# lcd_display_board.net
KiCad netlist of a schematic drawn in EAGLE
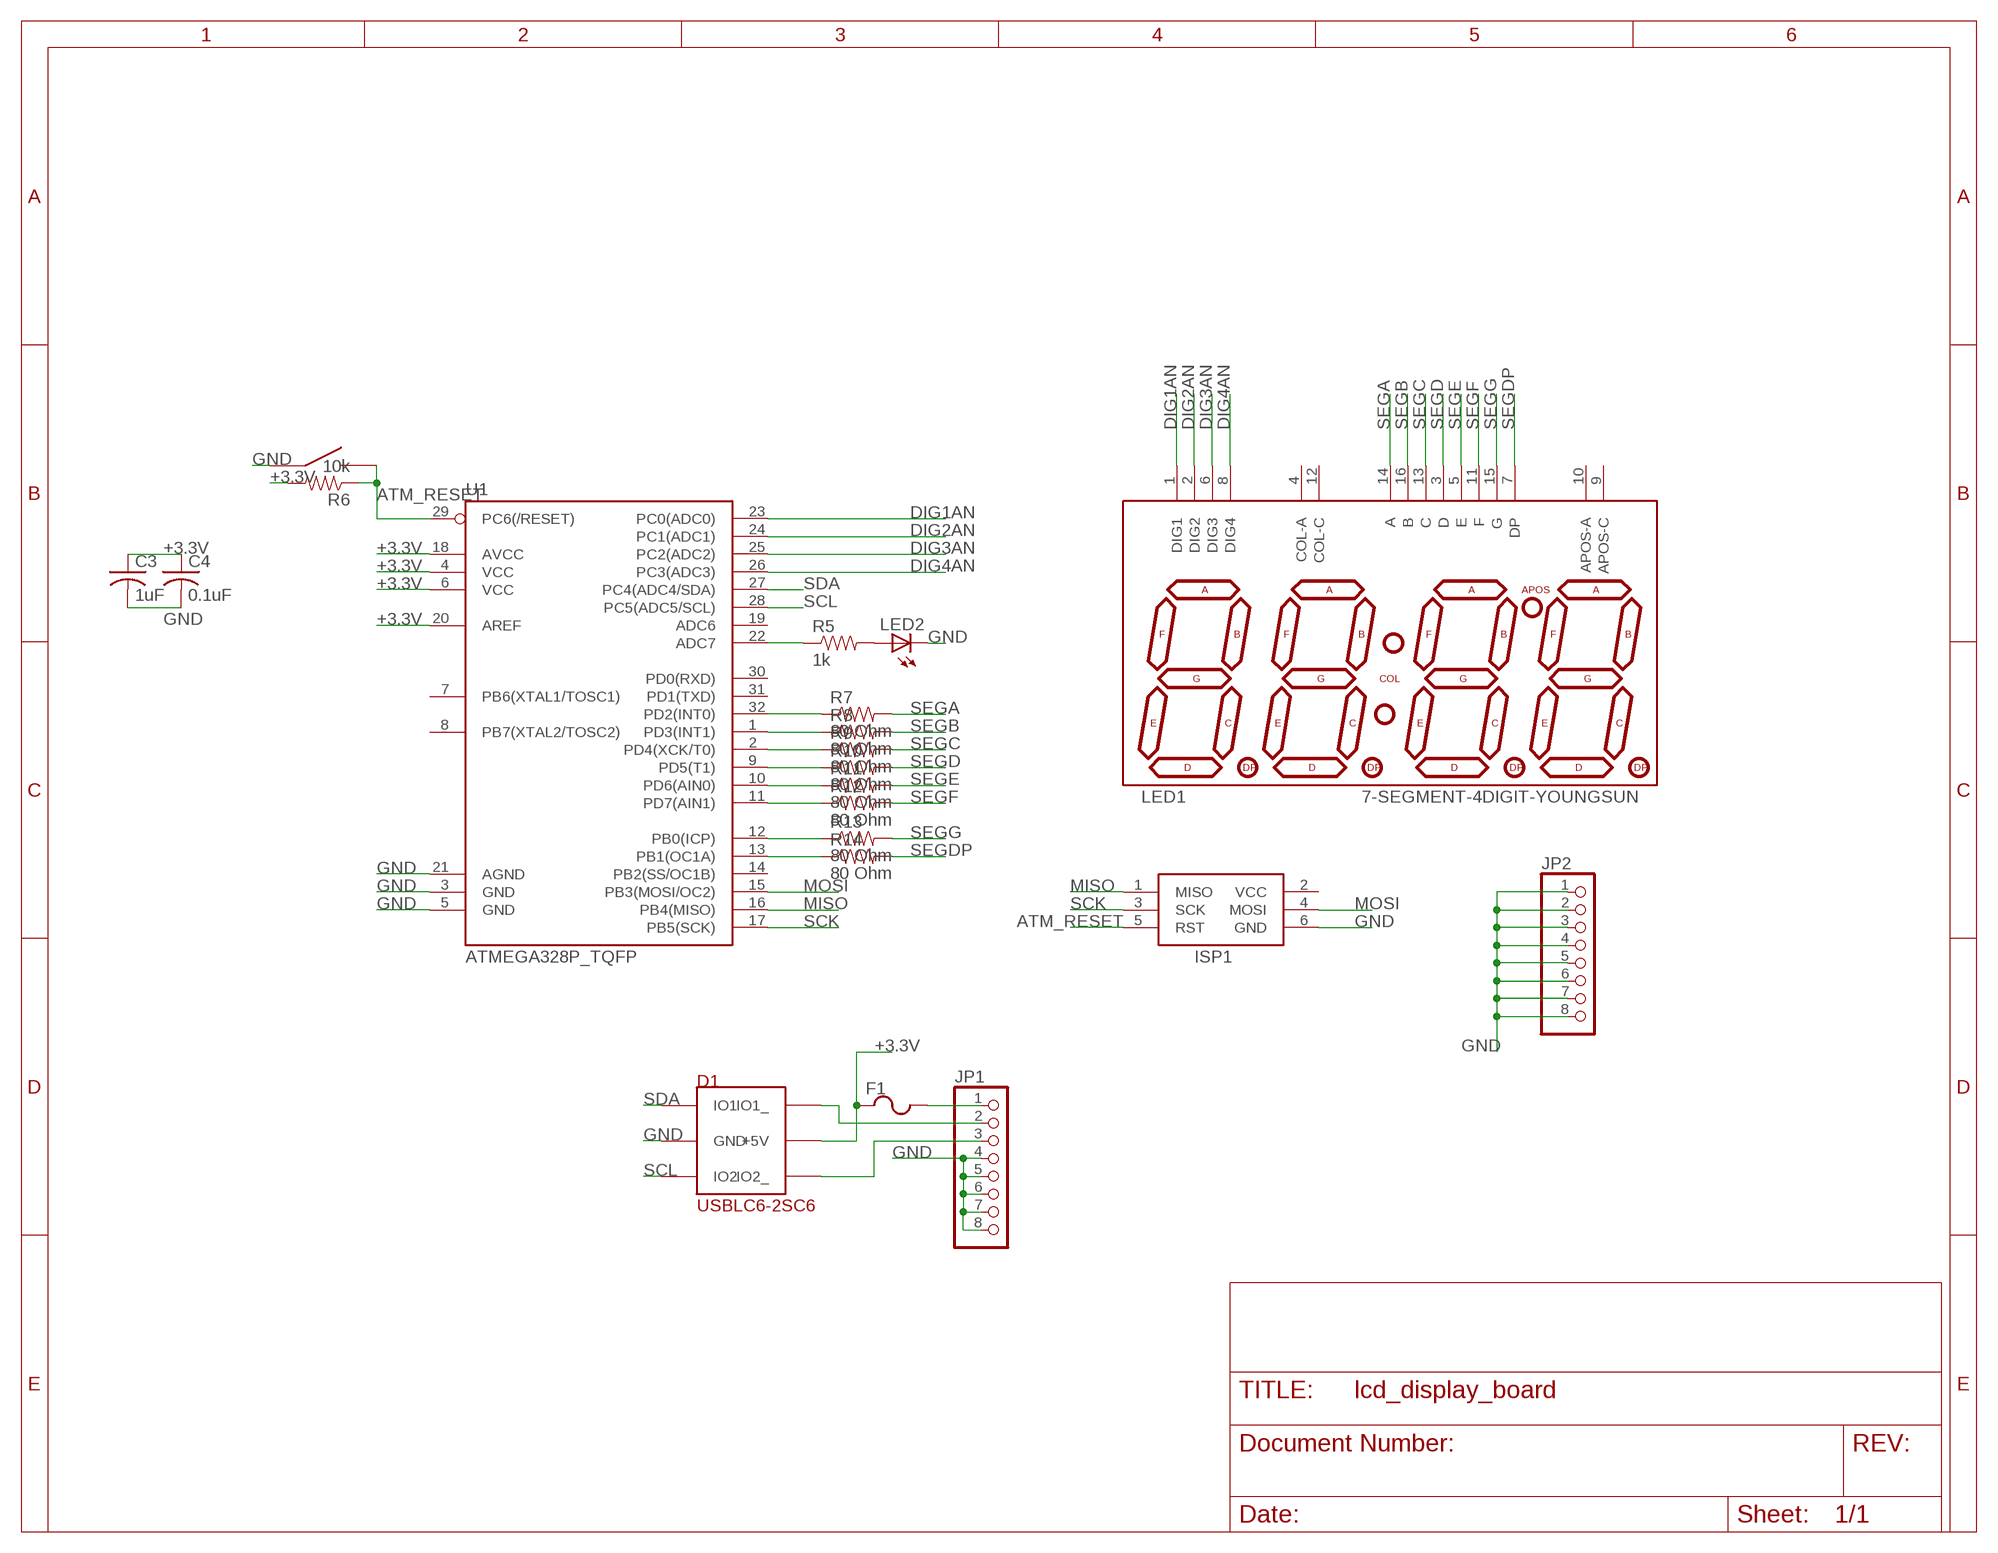
[diagram p0: schematic, sheet 1]

(export (version "E")
  (design (tool "Eeschema 10.0.6"))
  (components
    (comp (ref "C3")
      (value "1uF")
      (footprint "eagle-import:C0805")
      (libsource (lib "eagle-import") (part "C-USC0805"))
    )
    (comp (ref "C4")
      (value "0.1uF")
      (footprint "eagle-import:C0805")
      (libsource (lib "eagle-import") (part "C-USC0805"))
    )
    (comp (ref "D1")
      (value "USBLC6-2SC6")
      (footprint "eagle-import:USBLC6-2SC6")
      (libsource (lib "eagle-import") (part "USBLC6-2SC6"))
    )
    (comp (ref "F1")
      (value "POLYFUSE")
      (footprint "eagle-import:1206")
      (libsource (lib "eagle-import") (part "POLYFUSE"))
    )
    (comp (ref "ISP1")
      (value "AVRISP-BOX")
      (footprint "eagle-import:AVRISP-BOX")
      (libsource (lib "eagle-import") (part "AVRISP-BOX"))
    )
    (comp (ref "JP1")
      (value "PINHD-1X8BIG")
      (footprint "eagle-import:1X08-BIG")
      (libsource (lib "eagle-import") (part "PINHD-1X8BIG"))
    )
    (comp (ref "JP2")
      (value "PINHD-1X8BIG")
      (footprint "eagle-import:1X08-BIG")
      (libsource (lib "eagle-import") (part "PINHD-1X8BIG"))
    )
    (comp (ref "LED1")
      (value "7-SEGMENT-4DIGIT-YOUNGSUN")
      (footprint "eagle-import:7-SEGMENT-4DIGIT-YOUNGSUN")
      (libsource (lib "eagle-import") (part "7-SEGMENT-4DIGIT-YOUNGSUN"))
    )
    (comp (ref "LED2")
      (value "LEDCHIPLED_0805")
      (footprint "eagle-import:CHIPLED_0805")
      (libsource (lib "eagle-import") (part "LEDCHIPLED_0805"))
    )
    (comp (ref "R5")
      (value "1k")
      (footprint "eagle-import:0603-RES")
      (libsource (lib "eagle-import") (part "RESISTOR0603-RES"))
    )
    (comp (ref "R6")
      (value "10k")
      (footprint "eagle-import:0603-RES")
      (libsource (lib "eagle-import") (part "RESISTOR0603-RES"))
    )
    (comp (ref "R7")
      (value "80 Ohm")
      (footprint "eagle-import:0603-RES")
      (libsource (lib "eagle-import") (part "RESISTOR0603-RES"))
    )
    (comp (ref "R8")
      (value "80 Ohm")
      (footprint "eagle-import:0603-RES")
      (libsource (lib "eagle-import") (part "RESISTOR0603-RES"))
    )
    (comp (ref "R9")
      (value "80 Ohm")
      (footprint "eagle-import:0603-RES")
      (libsource (lib "eagle-import") (part "RESISTOR0603-RES"))
    )
    (comp (ref "R10")
      (value "80 Ohm")
      (footprint "eagle-import:0603-RES")
      (libsource (lib "eagle-import") (part "RESISTOR0603-RES"))
    )
    (comp (ref "R11")
      (value "80 Ohm")
      (footprint "eagle-import:0603-RES")
      (libsource (lib "eagle-import") (part "RESISTOR0603-RES"))
    )
    (comp (ref "R12")
      (value "80 Ohm")
      (footprint "eagle-import:0603-RES")
      (libsource (lib "eagle-import") (part "RESISTOR0603-RES"))
    )
    (comp (ref "R13")
      (value "80 Ohm")
      (footprint "eagle-import:0603-RES")
      (libsource (lib "eagle-import") (part "RESISTOR0603-RES"))
    )
    (comp (ref "R14")
      (value "80 Ohm")
      (footprint "eagle-import:0603-RES")
      (libsource (lib "eagle-import") (part "RESISTOR0603-RES"))
    )
    (comp (ref "U$10")
      (value "EG4621CT-ND")
      (footprint "eagle-import:EG4621CT-ND")
      (libsource (lib "eagle-import") (part "EG4621CT-ND"))
    )
    (comp (ref "U1")
      (value "ATMEGA328P_TQFP")
      (footprint "eagle-import:TQFP32-08")
      (libsource (lib "eagle-import") (part "ATMEGA328P_TQFP"))
    )
  )
  (nets
    (net (code "1") (name "/+3.3V") (class "Default")
      (node (ref "C3") (pin "1") (pinfunction "1_1") (pintype "passive"))
      (node (ref "C4") (pin "1") (pinfunction "1_1") (pintype "passive"))
      (node (ref "D1") (pin "P$5") (pinfunction "+5V_P$5") (pintype "bidirectional"))
      (node (ref "F1") (pin "1") (pinfunction "1_1") (pintype "passive"))
      (node (ref "R6") (pin "2") (pinfunction "2_2") (pintype "passive"))
      (node (ref "U1") (pin "18") (pinfunction "AVCC_18") (pintype "bidirectional"))
      (node (ref "U1") (pin "20") (pinfunction "AREF_20") (pintype "bidirectional"))
      (node (ref "U1") (pin "4") (pinfunction "VCC_4") (pintype "bidirectional"))
      (node (ref "U1") (pin "6") (pinfunction "VCC_6") (pintype "bidirectional"))
    )
    (net (code "2") (name "/ATM_RESET") (class "Default")
      (node (ref "ISP1") (pin "5") (pinfunction "RST_5") (pintype "output"))
      (node (ref "R6") (pin "1") (pinfunction "1_1") (pintype "passive"))
      (node (ref "U$10") (pin "P$3") (pinfunction "P$2_P$3") (pintype "bidirectional"))
      (node (ref "U$10") (pin "P$4") (pinfunction "P$2_P$4") (pintype "bidirectional"))
      (node (ref "U1") (pin "29") (pinfunction "PC6(/RESET)_29") (pintype "bidirectional"))
    )
    (net (code "3") (name "/DIG1AN") (class "Default")
      (node (ref "LED1") (pin "1") (pinfunction "DIG1_1") (pintype "bidirectional"))
      (node (ref "U1") (pin "23") (pinfunction "PC0(ADC0)_23") (pintype "bidirectional"))
    )
    (net (code "4") (name "/DIG2AN") (class "Default")
      (node (ref "LED1") (pin "2") (pinfunction "DIG2_2") (pintype "bidirectional"))
      (node (ref "U1") (pin "24") (pinfunction "PC1(ADC1)_24") (pintype "bidirectional"))
    )
    (net (code "5") (name "/DIG3AN") (class "Default")
      (node (ref "LED1") (pin "6") (pinfunction "DIG3_6") (pintype "bidirectional"))
      (node (ref "U1") (pin "25") (pinfunction "PC2(ADC2)_25") (pintype "bidirectional"))
    )
    (net (code "6") (name "/DIG4AN") (class "Default")
      (node (ref "LED1") (pin "8") (pinfunction "DIG4_8") (pintype "bidirectional"))
      (node (ref "U1") (pin "26") (pinfunction "PC3(ADC3)_26") (pintype "bidirectional"))
    )
    (net (code "7") (name "/GND") (class "Default")
      (node (ref "C3") (pin "2") (pinfunction "2_2") (pintype "passive"))
      (node (ref "C4") (pin "2") (pinfunction "2_2") (pintype "passive"))
      (node (ref "D1") (pin "P$2") (pinfunction "GND_P$2") (pintype "bidirectional"))
      (node (ref "ISP1") (pin "6") (pinfunction "GND_6") (pintype "power_in"))
      (node (ref "JP1") (pin "4") (pinfunction "4_4") (pintype "passive"))
      (node (ref "JP1") (pin "5") (pinfunction "5_5") (pintype "passive"))
      (node (ref "JP1") (pin "6") (pinfunction "6_6") (pintype "passive"))
      (node (ref "JP1") (pin "7") (pinfunction "7_7") (pintype "passive"))
      (node (ref "JP1") (pin "8") (pinfunction "8_8") (pintype "passive"))
      (node (ref "JP2") (pin "1") (pinfunction "1_1") (pintype "passive"))
      (node (ref "JP2") (pin "2") (pinfunction "2_2") (pintype "passive"))
      (node (ref "JP2") (pin "3") (pinfunction "3_3") (pintype "passive"))
      (node (ref "JP2") (pin "4") (pinfunction "4_4") (pintype "passive"))
      (node (ref "JP2") (pin "5") (pinfunction "5_5") (pintype "passive"))
      (node (ref "JP2") (pin "6") (pinfunction "6_6") (pintype "passive"))
      (node (ref "JP2") (pin "7") (pinfunction "7_7") (pintype "passive"))
      (node (ref "JP2") (pin "8") (pinfunction "8_8") (pintype "passive"))
      (node (ref "LED2") (pin "C") (pinfunction "C_C") (pintype "passive"))
      (node (ref "U$10") (pin "P$1") (pinfunction "P$1_P$1") (pintype "bidirectional"))
      (node (ref "U$10") (pin "P$2") (pinfunction "P$1_P$2") (pintype "bidirectional"))
      (node (ref "U1") (pin "21") (pinfunction "AGND_21") (pintype "bidirectional"))
      (node (ref "U1") (pin "3") (pinfunction "GND_3") (pintype "bidirectional"))
      (node (ref "U1") (pin "5") (pinfunction "GND_5") (pintype "bidirectional"))
    )
    (net (code "8") (name "/MISO") (class "Default")
      (node (ref "ISP1") (pin "1") (pinfunction "MISO_1") (pintype "input"))
      (node (ref "U1") (pin "16") (pinfunction "PB4(MISO)_16") (pintype "bidirectional"))
    )
    (net (code "9") (name "/MOSI") (class "Default")
      (node (ref "ISP1") (pin "4") (pinfunction "MOSI_4") (pintype "output"))
      (node (ref "U1") (pin "15") (pinfunction "PB3(MOSI/OC2)_15") (pintype "bidirectional"))
    )
    (net (code "10") (name "/SCK") (class "Default")
      (node (ref "ISP1") (pin "3") (pinfunction "SCK_3") (pintype "output"))
      (node (ref "U1") (pin "17") (pinfunction "PB5(SCK)_17") (pintype "bidirectional"))
    )
    (net (code "11") (name "/SCL") (class "Default")
      (node (ref "D1") (pin "P$3") (pinfunction "IO2_P$3") (pintype "bidirectional"))
      (node (ref "U1") (pin "28") (pinfunction "PC5(ADC5/SCL)_28") (pintype "bidirectional"))
    )
    (net (code "12") (name "/SDA") (class "Default")
      (node (ref "D1") (pin "P$1") (pinfunction "IO1_P$1") (pintype "bidirectional"))
      (node (ref "U1") (pin "27") (pinfunction "PC4(ADC4/SDA)_27") (pintype "bidirectional"))
    )
    (net (code "13") (name "/SEGA") (class "Default")
      (node (ref "LED1") (pin "14") (pinfunction "A_14") (pintype "bidirectional"))
      (node (ref "R7") (pin "2") (pinfunction "2_2") (pintype "passive"))
    )
    (net (code "14") (name "/SEGB") (class "Default")
      (node (ref "LED1") (pin "16") (pinfunction "B_16") (pintype "bidirectional"))
      (node (ref "R8") (pin "2") (pinfunction "2_2") (pintype "passive"))
    )
    (net (code "15") (name "/SEGC") (class "Default")
      (node (ref "LED1") (pin "13") (pinfunction "C_13") (pintype "bidirectional"))
      (node (ref "R9") (pin "2") (pinfunction "2_2") (pintype "passive"))
    )
    (net (code "16") (name "/SEGD") (class "Default")
      (node (ref "LED1") (pin "3") (pinfunction "D_3") (pintype "bidirectional"))
      (node (ref "R10") (pin "2") (pinfunction "2_2") (pintype "passive"))
    )
    (net (code "17") (name "/SEGDP") (class "Default")
      (node (ref "LED1") (pin "7") (pinfunction "DP_7") (pintype "bidirectional"))
      (node (ref "R14") (pin "2") (pinfunction "2_2") (pintype "passive"))
    )
    (net (code "18") (name "/SEGE") (class "Default")
      (node (ref "LED1") (pin "5") (pinfunction "E_5") (pintype "bidirectional"))
      (node (ref "R11") (pin "2") (pinfunction "2_2") (pintype "passive"))
    )
    (net (code "19") (name "/SEGF") (class "Default")
      (node (ref "LED1") (pin "11") (pinfunction "F_11") (pintype "bidirectional"))
      (node (ref "R12") (pin "2") (pinfunction "2_2") (pintype "passive"))
    )
    (net (code "20") (name "/SEGG") (class "Default")
      (node (ref "LED1") (pin "15") (pinfunction "G_15") (pintype "bidirectional"))
      (node (ref "R13") (pin "2") (pinfunction "2_2") (pintype "passive"))
    )
    (net (code "21") (name "/VCC") (class "Default")
      (node (ref "ISP1") (pin "2") (pinfunction "VCC_2") (pintype "power_in"))
    )
    (net (code "22") (name "Net-(D1-IO1_)") (class "Default")
      (node (ref "D1") (pin "P$6") (pinfunction "IO1__P$6") (pintype "bidirectional"))
      (node (ref "JP1") (pin "2") (pinfunction "2_2") (pintype "passive"))
    )
    (net (code "23") (name "Net-(D1-IO2_)") (class "Default")
      (node (ref "D1") (pin "P$4") (pinfunction "IO2__P$4") (pintype "bidirectional"))
      (node (ref "JP1") (pin "3") (pinfunction "3_3") (pintype "passive"))
    )
    (net (code "24") (name "Net-(F1-Pad2)") (class "Default")
      (node (ref "F1") (pin "2") (pinfunction "2_2") (pintype "passive"))
      (node (ref "JP1") (pin "1") (pinfunction "1_1") (pintype "passive"))
    )
    (net (code "25") (name "Net-(LED2-PadA)") (class "Default")
      (node (ref "LED2") (pin "A") (pinfunction "A_A") (pintype "passive"))
      (node (ref "R5") (pin "2") (pinfunction "2_2") (pintype "passive"))
    )
    (net (code "26") (name "Net-(U1-ADC7)") (class "Default")
      (node (ref "R5") (pin "1") (pinfunction "1_1") (pintype "passive"))
      (node (ref "U1") (pin "22") (pinfunction "ADC7_22") (pintype "bidirectional"))
    )
    (net (code "27") (name "Net-(U1-PB0(ICP))") (class "Default")
      (node (ref "R13") (pin "1") (pinfunction "1_1") (pintype "passive"))
      (node (ref "U1") (pin "12") (pinfunction "PB0(ICP)_12") (pintype "bidirectional"))
    )
    (net (code "28") (name "Net-(U1-PB1(OC1A))") (class "Default")
      (node (ref "R14") (pin "1") (pinfunction "1_1") (pintype "passive"))
      (node (ref "U1") (pin "13") (pinfunction "PB1(OC1A)_13") (pintype "bidirectional"))
    )
    (net (code "29") (name "Net-(U1-PD2(INT0))") (class "Default")
      (node (ref "R7") (pin "1") (pinfunction "1_1") (pintype "passive"))
      (node (ref "U1") (pin "32") (pinfunction "PD2(INT0)_32") (pintype "bidirectional"))
    )
    (net (code "30") (name "Net-(U1-PD3(INT1))") (class "Default")
      (node (ref "R8") (pin "1") (pinfunction "1_1") (pintype "passive"))
      (node (ref "U1") (pin "1") (pinfunction "PD3(INT1)_1") (pintype "bidirectional"))
    )
    (net (code "31") (name "Net-(U1-PD4(XCK{slash}T0))") (class "Default")
      (node (ref "R9") (pin "1") (pinfunction "1_1") (pintype "passive"))
      (node (ref "U1") (pin "2") (pinfunction "PD4(XCK/T0)_2") (pintype "bidirectional"))
    )
    (net (code "32") (name "Net-(U1-PD5(T1))") (class "Default")
      (node (ref "R10") (pin "1") (pinfunction "1_1") (pintype "passive"))
      (node (ref "U1") (pin "9") (pinfunction "PD5(T1)_9") (pintype "bidirectional"))
    )
    (net (code "33") (name "Net-(U1-PD6(AIN0))") (class "Default")
      (node (ref "R11") (pin "1") (pinfunction "1_1") (pintype "passive"))
      (node (ref "U1") (pin "10") (pinfunction "PD6(AIN0)_10") (pintype "bidirectional"))
    )
    (net (code "34") (name "Net-(U1-PD7(AIN1))") (class "Default")
      (node (ref "R12") (pin "1") (pinfunction "1_1") (pintype "passive"))
      (node (ref "U1") (pin "11") (pinfunction "PD7(AIN1)_11") (pintype "bidirectional"))
    )
    (net (code "35") (name "unconnected-(LED1-APOS-A-Pad10)") (class "Default")
      (node (ref "LED1") (pin "10") (pinfunction "APOS-A_10") (pintype "bidirectional"))
    )
    (net (code "36") (name "unconnected-(LED1-APOS-C-Pad9)") (class "Default")
      (node (ref "LED1") (pin "9") (pinfunction "APOS-C_9") (pintype "bidirectional"))
    )
    (net (code "37") (name "unconnected-(LED1-COL-A-Pad4)") (class "Default")
      (node (ref "LED1") (pin "4") (pinfunction "COL-A_4") (pintype "bidirectional"))
    )
    (net (code "38") (name "unconnected-(LED1-COL-C-Pad12)") (class "Default")
      (node (ref "LED1") (pin "12") (pinfunction "COL-C_12") (pintype "bidirectional"))
    )
    (net (code "39") (name "unconnected-(U1-ADC6-Pad19)") (class "Default")
      (node (ref "U1") (pin "19") (pinfunction "ADC6_19") (pintype "bidirectional"))
    )
    (net (code "40") (name "unconnected-(U1-PB2(SS{slash}OC1B)-Pad14)") (class "Default")
      (node (ref "U1") (pin "14") (pinfunction "PB2(SS/OC1B)_14") (pintype "bidirectional"))
    )
    (net (code "41") (name "unconnected-(U1-PB6(XTAL1{slash}TOSC1)-Pad7)") (class "Default")
      (node (ref "U1") (pin "7") (pinfunction "PB6(XTAL1/TOSC1)_7") (pintype "bidirectional"))
    )
    (net (code "42") (name "unconnected-(U1-PB7(XTAL2{slash}TOSC2)-Pad8)") (class "Default")
      (node (ref "U1") (pin "8") (pinfunction "PB7(XTAL2/TOSC2)_8") (pintype "bidirectional"))
    )
    (net (code "43") (name "unconnected-(U1-PD0(RXD)-Pad30)") (class "Default")
      (node (ref "U1") (pin "30") (pinfunction "PD0(RXD)_30") (pintype "bidirectional"))
    )
    (net (code "44") (name "unconnected-(U1-PD1(TXD)-Pad31)") (class "Default")
      (node (ref "U1") (pin "31") (pinfunction "PD1(TXD)_31") (pintype "bidirectional"))
    )
  )
)
